# balance.net
KiCad netlist of a schematic drawn in EAGLE
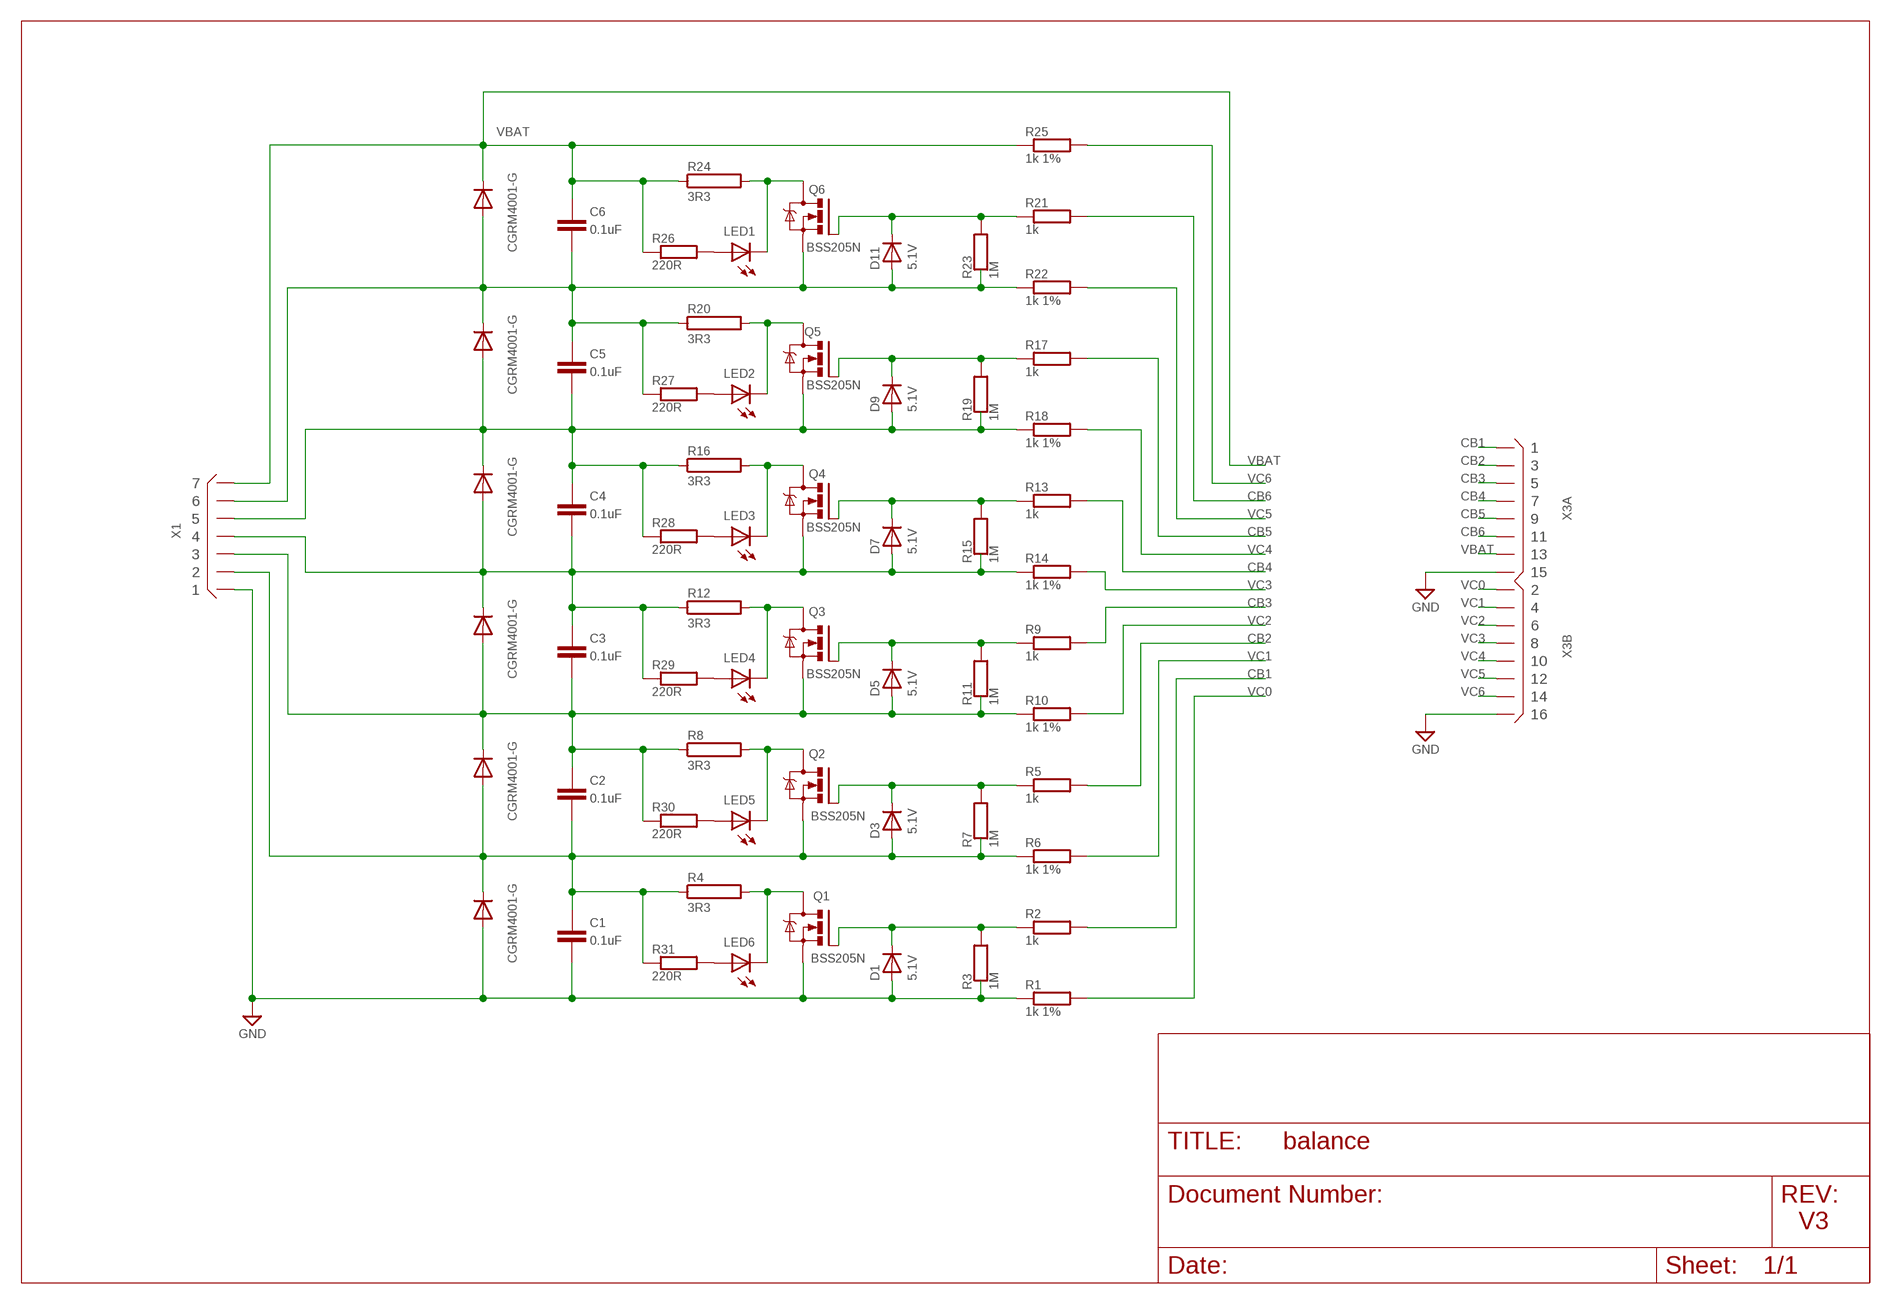
[diagram p0: schematic, sheet 1]

(export (version "E")
  (design (tool "Eeschema 10.0.6"))
  (components
    (comp (ref "C1")
      (value "0.1uF")
      (footprint "eagle-import:C0805")
      (libsource (lib "eagle-import") (part "CSTD"))
    )
    (comp (ref "C2")
      (value "0.1uF")
      (footprint "eagle-import:C0805")
      (libsource (lib "eagle-import") (part "CSTD"))
    )
    (comp (ref "C3")
      (value "0.1uF")
      (footprint "eagle-import:C0805")
      (libsource (lib "eagle-import") (part "CSTD"))
    )
    (comp (ref "C4")
      (value "0.1uF")
      (footprint "eagle-import:C0805")
      (libsource (lib "eagle-import") (part "CSTD"))
    )
    (comp (ref "C5")
      (value "0.1uF")
      (footprint "eagle-import:C0805")
      (libsource (lib "eagle-import") (part "CSTD"))
    )
    (comp (ref "C6")
      (value "0.1uF")
      (footprint "eagle-import:C0805")
      (libsource (lib "eagle-import") (part "CSTD"))
    )
    (comp (ref "D1")
      (value "5.1V")
      (footprint "eagle-import:SOD-323")
      (libsource (lib "eagle-import") (part "DIODESOD"))
    )
    (comp (ref "D2")
      (value "CGRM4001-G")
      (footprint "eagle-import:SOD-123_MINI-SMA")
      (libsource (lib "eagle-import") (part "CGRM400-G1"))
    )
    (comp (ref "D3")
      (value "5.1V")
      (footprint "eagle-import:SOD-323")
      (libsource (lib "eagle-import") (part "DIODESOD"))
    )
    (comp (ref "D4")
      (value "CGRM4001-G")
      (footprint "eagle-import:SOD-123_MINI-SMA")
      (libsource (lib "eagle-import") (part "CGRM400-G1"))
    )
    (comp (ref "D5")
      (value "5.1V")
      (footprint "eagle-import:SOD-323")
      (libsource (lib "eagle-import") (part "DIODESOD"))
    )
    (comp (ref "D6")
      (value "CGRM4001-G")
      (footprint "eagle-import:SOD-123_MINI-SMA")
      (libsource (lib "eagle-import") (part "CGRM400-G1"))
    )
    (comp (ref "D7")
      (value "5.1V")
      (footprint "eagle-import:SOD-323")
      (libsource (lib "eagle-import") (part "DIODESOD"))
    )
    (comp (ref "D8")
      (value "CGRM4001-G")
      (footprint "eagle-import:SOD-123_MINI-SMA")
      (libsource (lib "eagle-import") (part "CGRM400-G1"))
    )
    (comp (ref "D9")
      (value "5.1V")
      (footprint "eagle-import:SOD-323")
      (libsource (lib "eagle-import") (part "DIODESOD"))
    )
    (comp (ref "D10")
      (value "CGRM4001-G")
      (footprint "eagle-import:SOD-123_MINI-SMA")
      (libsource (lib "eagle-import") (part "CGRM400-G1"))
    )
    (comp (ref "D11")
      (value "5.1V")
      (footprint "eagle-import:SOD-323")
      (libsource (lib "eagle-import") (part "DIODESOD"))
    )
    (comp (ref "D12")
      (value "CGRM4001-G")
      (footprint "eagle-import:SOD-123_MINI-SMA")
      (libsource (lib "eagle-import") (part "CGRM400-G1"))
    )
    (comp (ref "LED1")
      (value "LEDCHIP-LED0805")
      (footprint "eagle-import:CHIP-LED0805")
      (libsource (lib "eagle-import") (part "LEDCHIP-LED0805"))
    )
    (comp (ref "LED2")
      (value "LEDCHIP-LED0805")
      (footprint "eagle-import:CHIP-LED0805")
      (libsource (lib "eagle-import") (part "LEDCHIP-LED0805"))
    )
    (comp (ref "LED3")
      (value "LEDCHIP-LED0805")
      (footprint "eagle-import:CHIP-LED0805")
      (libsource (lib "eagle-import") (part "LEDCHIP-LED0805"))
    )
    (comp (ref "LED4")
      (value "LEDCHIP-LED0805")
      (footprint "eagle-import:CHIP-LED0805")
      (libsource (lib "eagle-import") (part "LEDCHIP-LED0805"))
    )
    (comp (ref "LED5")
      (value "LEDCHIP-LED0805")
      (footprint "eagle-import:CHIP-LED0805")
      (libsource (lib "eagle-import") (part "LEDCHIP-LED0805"))
    )
    (comp (ref "LED6")
      (value "LEDCHIP-LED0805")
      (footprint "eagle-import:CHIP-LED0805")
      (libsource (lib "eagle-import") (part "LEDCHIP-LED0805"))
    )
    (comp (ref "Q1")
      (value "BSS205N")
      (footprint "eagle-import:SOT23")
      (libsource (lib "eagle-import") (part "BSS205N"))
    )
    (comp (ref "Q2")
      (value "BSS205N")
      (footprint "eagle-import:SOT23")
      (libsource (lib "eagle-import") (part "BSS205N"))
    )
    (comp (ref "Q3")
      (value "BSS205N")
      (footprint "eagle-import:SOT23")
      (libsource (lib "eagle-import") (part "BSS205N"))
    )
    (comp (ref "Q4")
      (value "BSS205N")
      (footprint "eagle-import:SOT23")
      (libsource (lib "eagle-import") (part "BSS205N"))
    )
    (comp (ref "Q5")
      (value "BSS205N")
      (footprint "eagle-import:SOT23")
      (libsource (lib "eagle-import") (part "BSS205N"))
    )
    (comp (ref "Q6")
      (value "BSS205N")
      (footprint "eagle-import:SOT23")
      (libsource (lib "eagle-import") (part "BSS205N"))
    )
    (comp (ref "R1")
      (value "1k 1%")
      (footprint "eagle-import:R0805")
      (libsource (lib "eagle-import") (part "useful_R"))
    )
    (comp (ref "R2")
      (value "1k")
      (footprint "eagle-import:R0805")
      (libsource (lib "eagle-import") (part "useful_R"))
    )
    (comp (ref "R3")
      (value "1M")
      (footprint "eagle-import:R0805")
      (libsource (lib "eagle-import") (part "useful_R"))
    )
    (comp (ref "R4")
      (value "3R3")
      (footprint "eagle-import:HS15")
      (libsource (lib "eagle-import") (part "R"))
    )
    (comp (ref "R5")
      (value "1k")
      (footprint "eagle-import:R0805")
      (libsource (lib "eagle-import") (part "useful_R"))
    )
    (comp (ref "R6")
      (value "1k 1%")
      (footprint "eagle-import:R0805")
      (libsource (lib "eagle-import") (part "useful_R"))
    )
    (comp (ref "R7")
      (value "1M")
      (footprint "eagle-import:R0805")
      (libsource (lib "eagle-import") (part "useful_R"))
    )
    (comp (ref "R8")
      (value "3R3")
      (footprint "eagle-import:HS15")
      (libsource (lib "eagle-import") (part "R"))
    )
    (comp (ref "R9")
      (value "1k")
      (footprint "eagle-import:R0805")
      (libsource (lib "eagle-import") (part "useful_R"))
    )
    (comp (ref "R10")
      (value "1k 1%")
      (footprint "eagle-import:R0805")
      (libsource (lib "eagle-import") (part "useful_R"))
    )
    (comp (ref "R11")
      (value "1M")
      (footprint "eagle-import:R0805")
      (libsource (lib "eagle-import") (part "useful_R"))
    )
    (comp (ref "R12")
      (value "3R3")
      (footprint "eagle-import:HS15")
      (libsource (lib "eagle-import") (part "R"))
    )
    (comp (ref "R13")
      (value "1k")
      (footprint "eagle-import:R0805")
      (libsource (lib "eagle-import") (part "useful_R"))
    )
    (comp (ref "R14")
      (value "1k 1%")
      (footprint "eagle-import:R0805")
      (libsource (lib "eagle-import") (part "useful_R"))
    )
    (comp (ref "R15")
      (value "1M")
      (footprint "eagle-import:R0805")
      (libsource (lib "eagle-import") (part "useful_R"))
    )
    (comp (ref "R16")
      (value "3R3")
      (footprint "eagle-import:HS15")
      (libsource (lib "eagle-import") (part "R"))
    )
    (comp (ref "R17")
      (value "1k")
      (footprint "eagle-import:R0805")
      (libsource (lib "eagle-import") (part "useful_R"))
    )
    (comp (ref "R18")
      (value "1k 1%")
      (footprint "eagle-import:R0805")
      (libsource (lib "eagle-import") (part "useful_R"))
    )
    (comp (ref "R19")
      (value "1M")
      (footprint "eagle-import:R0805")
      (libsource (lib "eagle-import") (part "useful_R"))
    )
    (comp (ref "R20")
      (value "3R3")
      (footprint "eagle-import:HS15")
      (libsource (lib "eagle-import") (part "R"))
    )
    (comp (ref "R21")
      (value "1k")
      (footprint "eagle-import:R0805")
      (libsource (lib "eagle-import") (part "useful_R"))
    )
    (comp (ref "R22")
      (value "1k 1%")
      (footprint "eagle-import:R0805")
      (libsource (lib "eagle-import") (part "useful_R"))
    )
    (comp (ref "R23")
      (value "1M")
      (footprint "eagle-import:R0805")
      (libsource (lib "eagle-import") (part "useful_R"))
    )
    (comp (ref "R24")
      (value "3R3")
      (footprint "eagle-import:HS15")
      (libsource (lib "eagle-import") (part "R"))
    )
    (comp (ref "R25")
      (value "1k 1%")
      (footprint "eagle-import:R0805")
      (libsource (lib "eagle-import") (part "useful_R"))
    )
    (comp (ref "R26")
      (value "220R")
      (footprint "eagle-import:R0805")
      (libsource (lib "eagle-import") (part "useful_R"))
    )
    (comp (ref "R27")
      (value "220R")
      (footprint "eagle-import:R0805")
      (libsource (lib "eagle-import") (part "useful_R"))
    )
    (comp (ref "R28")
      (value "220R")
      (footprint "eagle-import:R0805")
      (libsource (lib "eagle-import") (part "useful_R"))
    )
    (comp (ref "R29")
      (value "220R")
      (footprint "eagle-import:R0805")
      (libsource (lib "eagle-import") (part "useful_R"))
    )
    (comp (ref "R30")
      (value "220R")
      (footprint "eagle-import:R0805")
      (libsource (lib "eagle-import") (part "useful_R"))
    )
    (comp (ref "R31")
      (value "220R")
      (footprint "eagle-import:R0805")
      (libsource (lib "eagle-import") (part "useful_R"))
    )
    (comp (ref "X1")
      (value "B7B-XH")
      (footprint "eagle-import:B7B-XH")
      (libsource (lib "eagle-import") (part "?7B-XHB"))
    )
    (comp (ref "X3")
      (value "X08X2DR")
      (footprint "eagle-import:X16R-DIL")
      (libsource (lib "eagle-import") (part "X08X2DR"))
    )
  )
  (nets
    (net (code "1") (name "/CB1") (class "Default")
      (node (ref "R2") (pin "2") (pinfunction "2_2") (pintype "passive"))
      (node (ref "X3") (pin "1") (pinfunction "1_1") (pintype "bidirectional"))
    )
    (net (code "2") (name "/CB2") (class "Default")
      (node (ref "R5") (pin "2") (pinfunction "2_2") (pintype "passive"))
      (node (ref "X3") (pin "3") (pinfunction "3_3") (pintype "bidirectional"))
    )
    (net (code "3") (name "/CB3") (class "Default")
      (node (ref "R9") (pin "2") (pinfunction "2_2") (pintype "passive"))
      (node (ref "X3") (pin "5") (pinfunction "5_5") (pintype "bidirectional"))
    )
    (net (code "4") (name "/CB4") (class "Default")
      (node (ref "R13") (pin "2") (pinfunction "2_2") (pintype "passive"))
      (node (ref "X3") (pin "7") (pinfunction "7_7") (pintype "bidirectional"))
    )
    (net (code "5") (name "/CB5") (class "Default")
      (node (ref "R17") (pin "2") (pinfunction "2_2") (pintype "passive"))
      (node (ref "X3") (pin "9") (pinfunction "9_9") (pintype "bidirectional"))
    )
    (net (code "6") (name "/CB6") (class "Default")
      (node (ref "R21") (pin "2") (pinfunction "2_2") (pintype "passive"))
      (node (ref "X3") (pin "11") (pinfunction "11_11") (pintype "bidirectional"))
    )
    (net (code "7") (name "/VBAT") (class "Default")
      (node (ref "C6") (pin "2") (pinfunction "2_2") (pintype "passive"))
      (node (ref "D12") (pin "C") (pinfunction "C_C") (pintype "passive"))
      (node (ref "R24") (pin "1") (pinfunction "1_1") (pintype "passive"))
      (node (ref "R25") (pin "1") (pinfunction "1_1") (pintype "passive"))
      (node (ref "R26") (pin "1") (pinfunction "1_1") (pintype "passive"))
      (node (ref "X1") (pin "P$7") (pinfunction "7_P$7") (pintype "bidirectional"))
      (node (ref "X3") (pin "13") (pinfunction "13_13") (pintype "bidirectional"))
    )
    (net (code "8") (name "/VC0") (class "Default")
      (node (ref "R1") (pin "2") (pinfunction "2_2") (pintype "passive"))
      (node (ref "X3") (pin "2") (pinfunction "2_2") (pintype "bidirectional"))
    )
    (net (code "9") (name "/VC1") (class "Default")
      (node (ref "R6") (pin "2") (pinfunction "2_2") (pintype "passive"))
      (node (ref "X3") (pin "4") (pinfunction "4_4") (pintype "bidirectional"))
    )
    (net (code "10") (name "/VC2") (class "Default")
      (node (ref "R10") (pin "2") (pinfunction "2_2") (pintype "passive"))
      (node (ref "X3") (pin "6") (pinfunction "6_6") (pintype "bidirectional"))
    )
    (net (code "11") (name "/VC3") (class "Default")
      (node (ref "R14") (pin "2") (pinfunction "2_2") (pintype "passive"))
      (node (ref "X3") (pin "8") (pinfunction "8_8") (pintype "bidirectional"))
    )
    (net (code "12") (name "/VC4") (class "Default")
      (node (ref "R18") (pin "2") (pinfunction "2_2") (pintype "passive"))
      (node (ref "X3") (pin "10") (pinfunction "10_10") (pintype "bidirectional"))
    )
    (net (code "13") (name "/VC5") (class "Default")
      (node (ref "R22") (pin "2") (pinfunction "2_2") (pintype "passive"))
      (node (ref "X3") (pin "12") (pinfunction "12_12") (pintype "bidirectional"))
    )
    (net (code "14") (name "/VC6") (class "Default")
      (node (ref "R25") (pin "2") (pinfunction "2_2") (pintype "passive"))
      (node (ref "X3") (pin "14") (pinfunction "14_14") (pintype "bidirectional"))
    )
    (net (code "15") (name "GND") (class "Default")
      (node (ref "C1") (pin "1") (pinfunction "1_1") (pintype "passive"))
      (node (ref "D1") (pin "2") (pinfunction "A_2") (pintype "passive"))
      (node (ref "D2") (pin "A") (pinfunction "A_A") (pintype "passive"))
      (node (ref "Q1") (pin "2") (pinfunction "S_2") (pintype "passive"))
      (node (ref "R1") (pin "1") (pinfunction "1_1") (pintype "passive"))
      (node (ref "R3") (pin "1") (pinfunction "1_1") (pintype "passive"))
      (node (ref "X1") (pin "P$1") (pinfunction "1_P$1") (pintype "bidirectional"))
      (node (ref "X3") (pin "15") (pinfunction "15_15") (pintype "bidirectional"))
      (node (ref "X3") (pin "16") (pinfunction "16_16") (pintype "bidirectional"))
    )
    (net (code "16") (name "Net-(D1-C)") (class "Default")
      (node (ref "D1") (pin "1") (pinfunction "C_1") (pintype "passive"))
      (node (ref "Q1") (pin "1") (pinfunction "G_1") (pintype "passive"))
      (node (ref "R2") (pin "1") (pinfunction "1_1") (pintype "passive"))
      (node (ref "R3") (pin "2") (pinfunction "2_2") (pintype "passive"))
    )
    (net (code "17") (name "Net-(D3-A)") (class "Default")
      (node (ref "C1") (pin "2") (pinfunction "2_2") (pintype "passive"))
      (node (ref "C2") (pin "1") (pinfunction "1_1") (pintype "passive"))
      (node (ref "D2") (pin "C") (pinfunction "C_C") (pintype "passive"))
      (node (ref "D3") (pin "2") (pinfunction "A_2") (pintype "passive"))
      (node (ref "D4") (pin "A") (pinfunction "A_A") (pintype "passive"))
      (node (ref "Q2") (pin "2") (pinfunction "S_2") (pintype "passive"))
      (node (ref "R31") (pin "1") (pinfunction "1_1") (pintype "passive"))
      (node (ref "R4") (pin "1") (pinfunction "1_1") (pintype "passive"))
      (node (ref "R6") (pin "1") (pinfunction "1_1") (pintype "passive"))
      (node (ref "R7") (pin "1") (pinfunction "1_1") (pintype "passive"))
      (node (ref "X1") (pin "P$2") (pinfunction "2_P$2") (pintype "bidirectional"))
    )
    (net (code "18") (name "Net-(D3-C)") (class "Default")
      (node (ref "D3") (pin "1") (pinfunction "C_1") (pintype "passive"))
      (node (ref "Q2") (pin "1") (pinfunction "G_1") (pintype "passive"))
      (node (ref "R5") (pin "1") (pinfunction "1_1") (pintype "passive"))
      (node (ref "R7") (pin "2") (pinfunction "2_2") (pintype "passive"))
    )
    (net (code "19") (name "Net-(D5-A)") (class "Default")
      (node (ref "C2") (pin "2") (pinfunction "2_2") (pintype "passive"))
      (node (ref "C3") (pin "1") (pinfunction "1_1") (pintype "passive"))
      (node (ref "D4") (pin "C") (pinfunction "C_C") (pintype "passive"))
      (node (ref "D5") (pin "2") (pinfunction "A_2") (pintype "passive"))
      (node (ref "D6") (pin "A") (pinfunction "A_A") (pintype "passive"))
      (node (ref "Q3") (pin "2") (pinfunction "S_2") (pintype "passive"))
      (node (ref "R10") (pin "1") (pinfunction "1_1") (pintype "passive"))
      (node (ref "R11") (pin "1") (pinfunction "1_1") (pintype "passive"))
      (node (ref "R30") (pin "1") (pinfunction "1_1") (pintype "passive"))
      (node (ref "R8") (pin "1") (pinfunction "1_1") (pintype "passive"))
      (node (ref "X1") (pin "P$3") (pinfunction "3_P$3") (pintype "bidirectional"))
    )
    (net (code "20") (name "Net-(D5-C)") (class "Default")
      (node (ref "D5") (pin "1") (pinfunction "C_1") (pintype "passive"))
      (node (ref "Q3") (pin "1") (pinfunction "G_1") (pintype "passive"))
      (node (ref "R11") (pin "2") (pinfunction "2_2") (pintype "passive"))
      (node (ref "R9") (pin "1") (pinfunction "1_1") (pintype "passive"))
    )
    (net (code "21") (name "Net-(D7-A)") (class "Default")
      (node (ref "C3") (pin "2") (pinfunction "2_2") (pintype "passive"))
      (node (ref "C4") (pin "1") (pinfunction "1_1") (pintype "passive"))
      (node (ref "D6") (pin "C") (pinfunction "C_C") (pintype "passive"))
      (node (ref "D7") (pin "2") (pinfunction "A_2") (pintype "passive"))
      (node (ref "D8") (pin "A") (pinfunction "A_A") (pintype "passive"))
      (node (ref "Q4") (pin "2") (pinfunction "S_2") (pintype "passive"))
      (node (ref "R12") (pin "1") (pinfunction "1_1") (pintype "passive"))
      (node (ref "R14") (pin "1") (pinfunction "1_1") (pintype "passive"))
      (node (ref "R15") (pin "1") (pinfunction "1_1") (pintype "passive"))
      (node (ref "R29") (pin "1") (pinfunction "1_1") (pintype "passive"))
      (node (ref "X1") (pin "P$4") (pinfunction "4_P$4") (pintype "bidirectional"))
    )
    (net (code "22") (name "Net-(D7-C)") (class "Default")
      (node (ref "D7") (pin "1") (pinfunction "C_1") (pintype "passive"))
      (node (ref "Q4") (pin "1") (pinfunction "G_1") (pintype "passive"))
      (node (ref "R13") (pin "1") (pinfunction "1_1") (pintype "passive"))
      (node (ref "R15") (pin "2") (pinfunction "2_2") (pintype "passive"))
    )
    (net (code "23") (name "Net-(D9-A)") (class "Default")
      (node (ref "C4") (pin "2") (pinfunction "2_2") (pintype "passive"))
      (node (ref "C5") (pin "1") (pinfunction "1_1") (pintype "passive"))
      (node (ref "D10") (pin "A") (pinfunction "A_A") (pintype "passive"))
      (node (ref "D8") (pin "C") (pinfunction "C_C") (pintype "passive"))
      (node (ref "D9") (pin "2") (pinfunction "A_2") (pintype "passive"))
      (node (ref "Q5") (pin "2") (pinfunction "S_2") (pintype "passive"))
      (node (ref "R16") (pin "1") (pinfunction "1_1") (pintype "passive"))
      (node (ref "R18") (pin "1") (pinfunction "1_1") (pintype "passive"))
      (node (ref "R19") (pin "1") (pinfunction "1_1") (pintype "passive"))
      (node (ref "R28") (pin "1") (pinfunction "1_1") (pintype "passive"))
      (node (ref "X1") (pin "P$5") (pinfunction "5_P$5") (pintype "bidirectional"))
    )
    (net (code "24") (name "Net-(D9-C)") (class "Default")
      (node (ref "D9") (pin "1") (pinfunction "C_1") (pintype "passive"))
      (node (ref "Q5") (pin "1") (pinfunction "G_1") (pintype "passive"))
      (node (ref "R17") (pin "1") (pinfunction "1_1") (pintype "passive"))
      (node (ref "R19") (pin "2") (pinfunction "2_2") (pintype "passive"))
    )
    (net (code "25") (name "Net-(D11-A)") (class "Default")
      (node (ref "C5") (pin "2") (pinfunction "2_2") (pintype "passive"))
      (node (ref "C6") (pin "1") (pinfunction "1_1") (pintype "passive"))
      (node (ref "D10") (pin "C") (pinfunction "C_C") (pintype "passive"))
      (node (ref "D11") (pin "2") (pinfunction "A_2") (pintype "passive"))
      (node (ref "D12") (pin "A") (pinfunction "A_A") (pintype "passive"))
      (node (ref "Q6") (pin "2") (pinfunction "S_2") (pintype "passive"))
      (node (ref "R20") (pin "1") (pinfunction "1_1") (pintype "passive"))
      (node (ref "R22") (pin "1") (pinfunction "1_1") (pintype "passive"))
      (node (ref "R23") (pin "1") (pinfunction "1_1") (pintype "passive"))
      (node (ref "R27") (pin "1") (pinfunction "1_1") (pintype "passive"))
      (node (ref "X1") (pin "P$6") (pinfunction "6_P$6") (pintype "bidirectional"))
    )
    (net (code "26") (name "Net-(D11-C)") (class "Default")
      (node (ref "D11") (pin "1") (pinfunction "C_1") (pintype "passive"))
      (node (ref "Q6") (pin "1") (pinfunction "G_1") (pintype "passive"))
      (node (ref "R21") (pin "1") (pinfunction "1_1") (pintype "passive"))
      (node (ref "R23") (pin "2") (pinfunction "2_2") (pintype "passive"))
    )
    (net (code "27") (name "Net-(LED1-PadA)") (class "Default")
      (node (ref "LED1") (pin "A") (pinfunction "A_A") (pintype "passive"))
      (node (ref "R26") (pin "2") (pinfunction "2_2") (pintype "passive"))
    )
    (net (code "28") (name "Net-(LED2-PadA)") (class "Default")
      (node (ref "LED2") (pin "A") (pinfunction "A_A") (pintype "passive"))
      (node (ref "R27") (pin "2") (pinfunction "2_2") (pintype "passive"))
    )
    (net (code "29") (name "Net-(LED3-PadA)") (class "Default")
      (node (ref "LED3") (pin "A") (pinfunction "A_A") (pintype "passive"))
      (node (ref "R28") (pin "2") (pinfunction "2_2") (pintype "passive"))
    )
    (net (code "30") (name "Net-(LED4-PadA)") (class "Default")
      (node (ref "LED4") (pin "A") (pinfunction "A_A") (pintype "passive"))
      (node (ref "R29") (pin "2") (pinfunction "2_2") (pintype "passive"))
    )
    (net (code "31") (name "Net-(LED5-PadA)") (class "Default")
      (node (ref "LED5") (pin "A") (pinfunction "A_A") (pintype "passive"))
      (node (ref "R30") (pin "2") (pinfunction "2_2") (pintype "passive"))
    )
    (net (code "32") (name "Net-(LED6-PadA)") (class "Default")
      (node (ref "LED6") (pin "A") (pinfunction "A_A") (pintype "passive"))
      (node (ref "R31") (pin "2") (pinfunction "2_2") (pintype "passive"))
    )
    (net (code "33") (name "Net-(Q1-D)") (class "Default")
      (node (ref "LED6") (pin "C") (pinfunction "C_C") (pintype "passive"))
      (node (ref "Q1") (pin "3") (pinfunction "D_3") (pintype "passive"))
      (node (ref "R4") (pin "2") (pinfunction "2_2") (pintype "passive"))
    )
    (net (code "34") (name "Net-(Q2-D)") (class "Default")
      (node (ref "LED5") (pin "C") (pinfunction "C_C") (pintype "passive"))
      (node (ref "Q2") (pin "3") (pinfunction "D_3") (pintype "passive"))
      (node (ref "R8") (pin "2") (pinfunction "2_2") (pintype "passive"))
    )
    (net (code "35") (name "Net-(Q3-D)") (class "Default")
      (node (ref "LED4") (pin "C") (pinfunction "C_C") (pintype "passive"))
      (node (ref "Q3") (pin "3") (pinfunction "D_3") (pintype "passive"))
      (node (ref "R12") (pin "2") (pinfunction "2_2") (pintype "passive"))
    )
    (net (code "36") (name "Net-(Q4-D)") (class "Default")
      (node (ref "LED3") (pin "C") (pinfunction "C_C") (pintype "passive"))
      (node (ref "Q4") (pin "3") (pinfunction "D_3") (pintype "passive"))
      (node (ref "R16") (pin "2") (pinfunction "2_2") (pintype "passive"))
    )
    (net (code "37") (name "Net-(Q5-D)") (class "Default")
      (node (ref "LED2") (pin "C") (pinfunction "C_C") (pintype "passive"))
      (node (ref "Q5") (pin "3") (pinfunction "D_3") (pintype "passive"))
      (node (ref "R20") (pin "2") (pinfunction "2_2") (pintype "passive"))
    )
    (net (code "38") (name "Net-(Q6-D)") (class "Default")
      (node (ref "LED1") (pin "C") (pinfunction "C_C") (pintype "passive"))
      (node (ref "Q6") (pin "3") (pinfunction "D_3") (pintype "passive"))
      (node (ref "R24") (pin "2") (pinfunction "2_2") (pintype "passive"))
    )
  )
)
